# Controller.net
KiCad netlist of a schematic drawn in Altium Designer
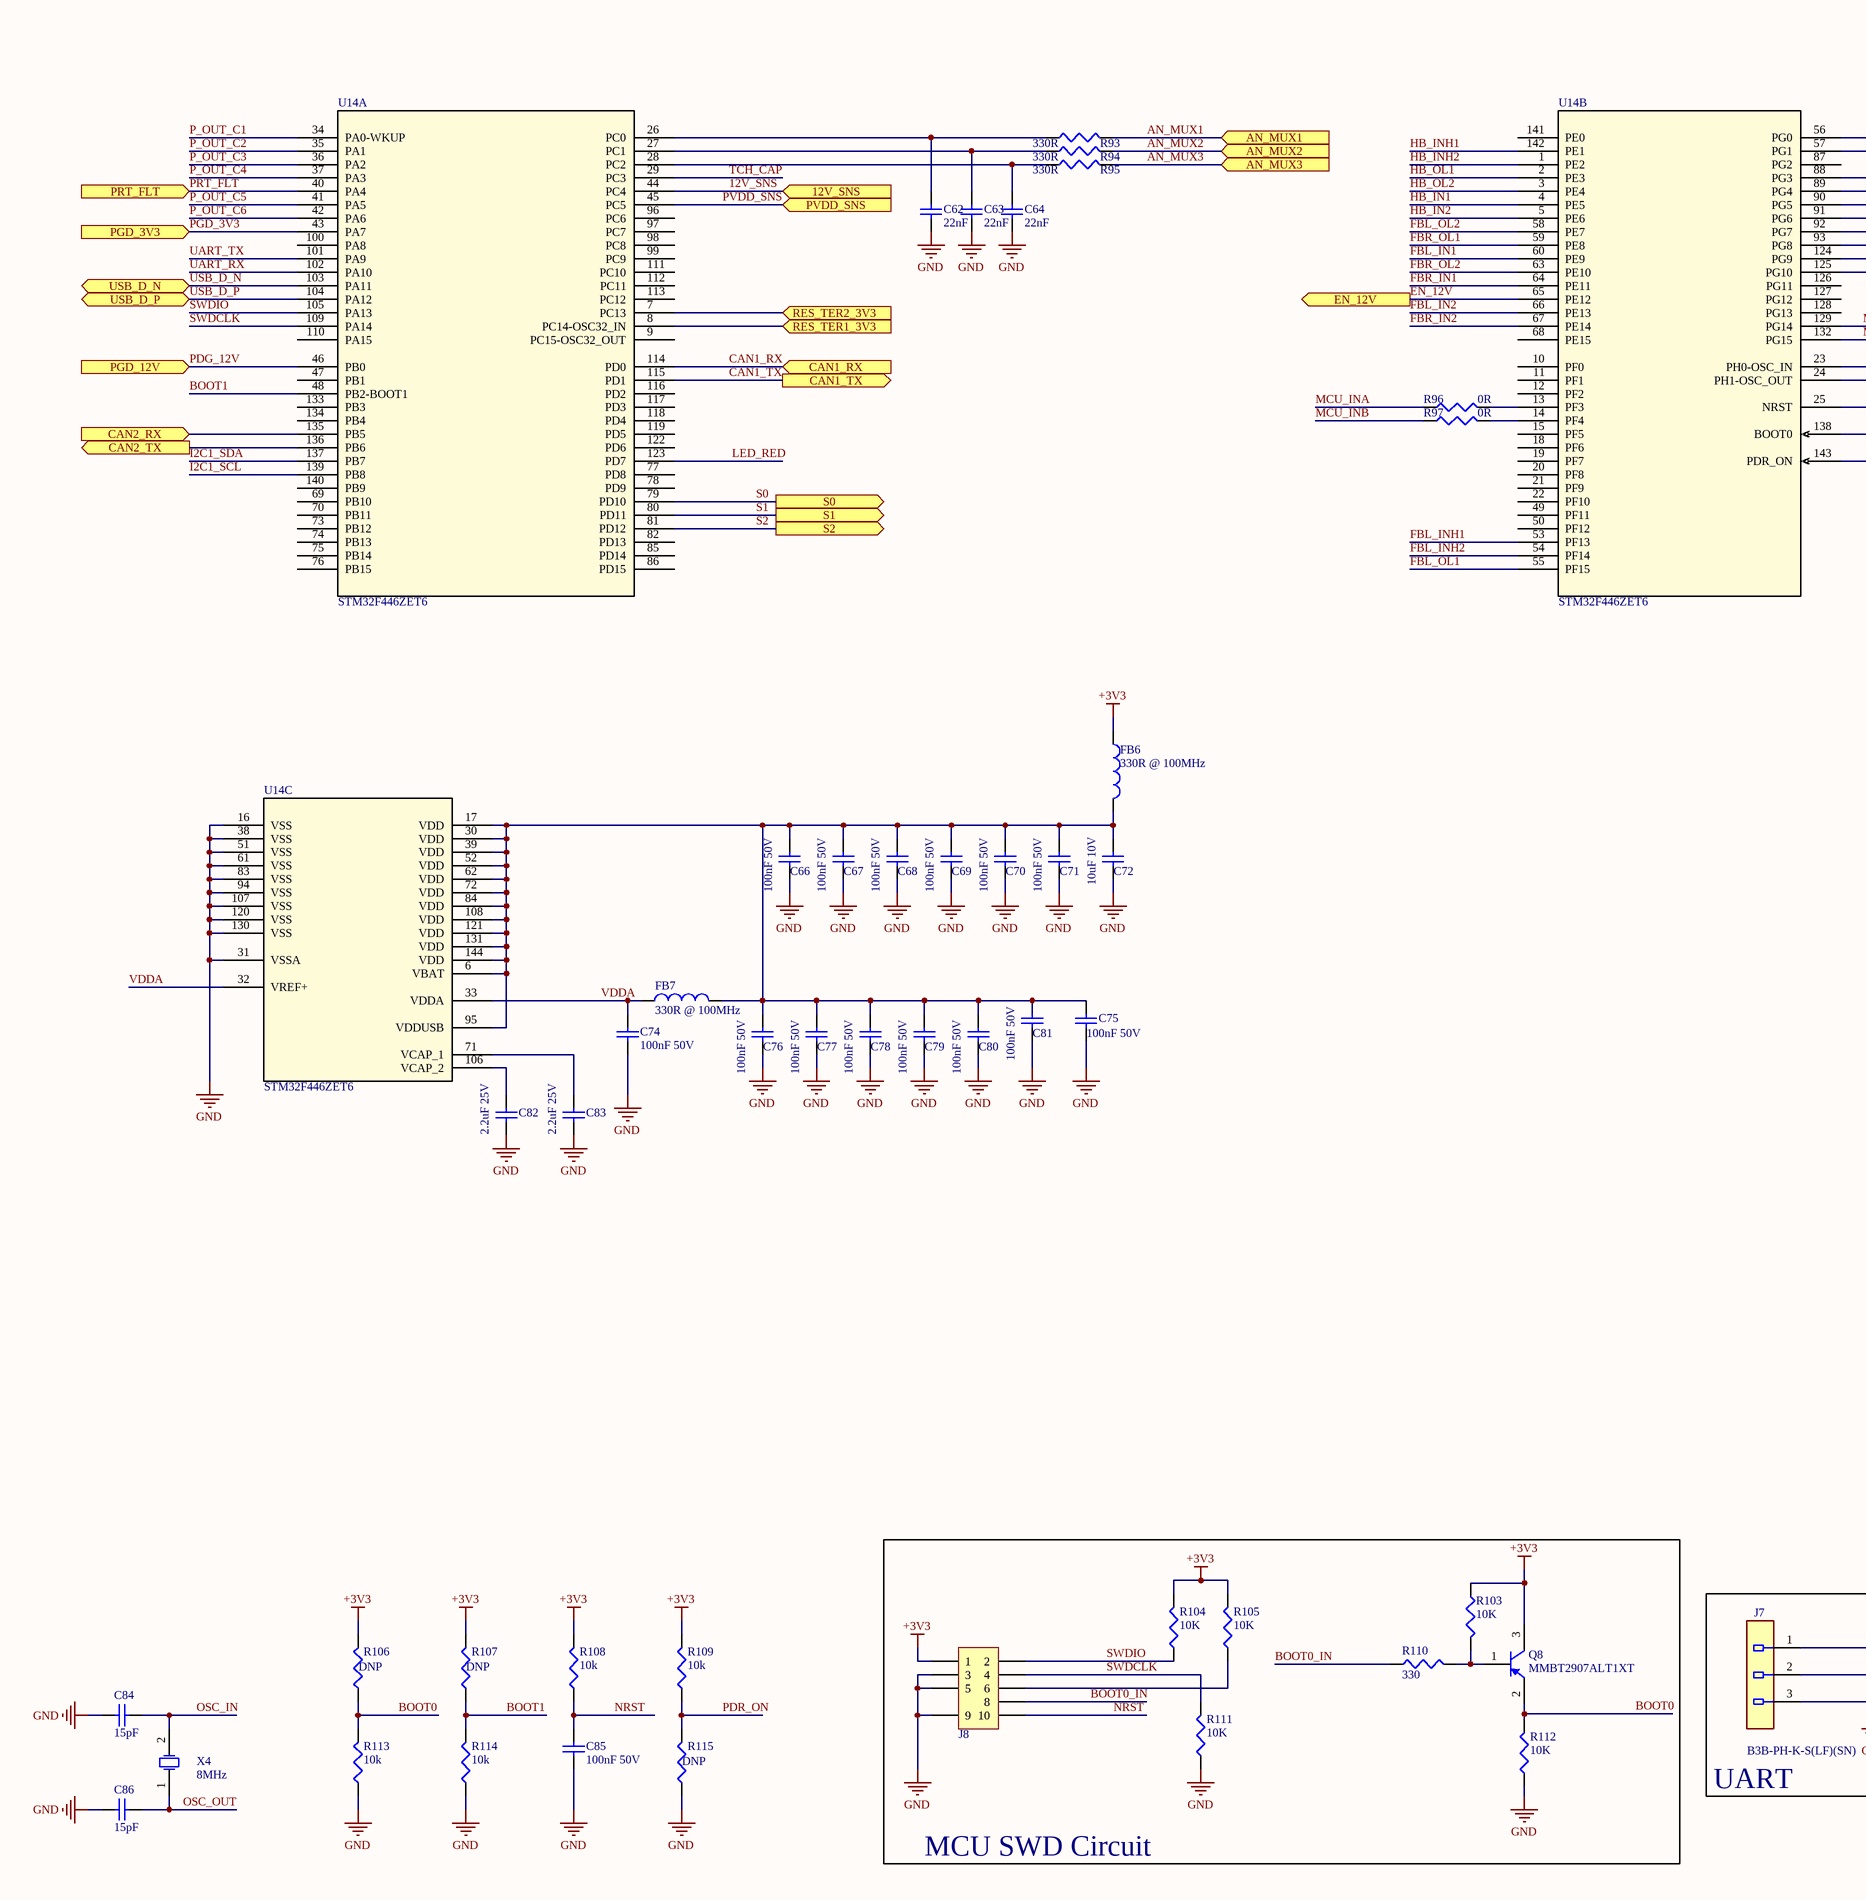
[diagram p0: Controller.SchDoc, left]
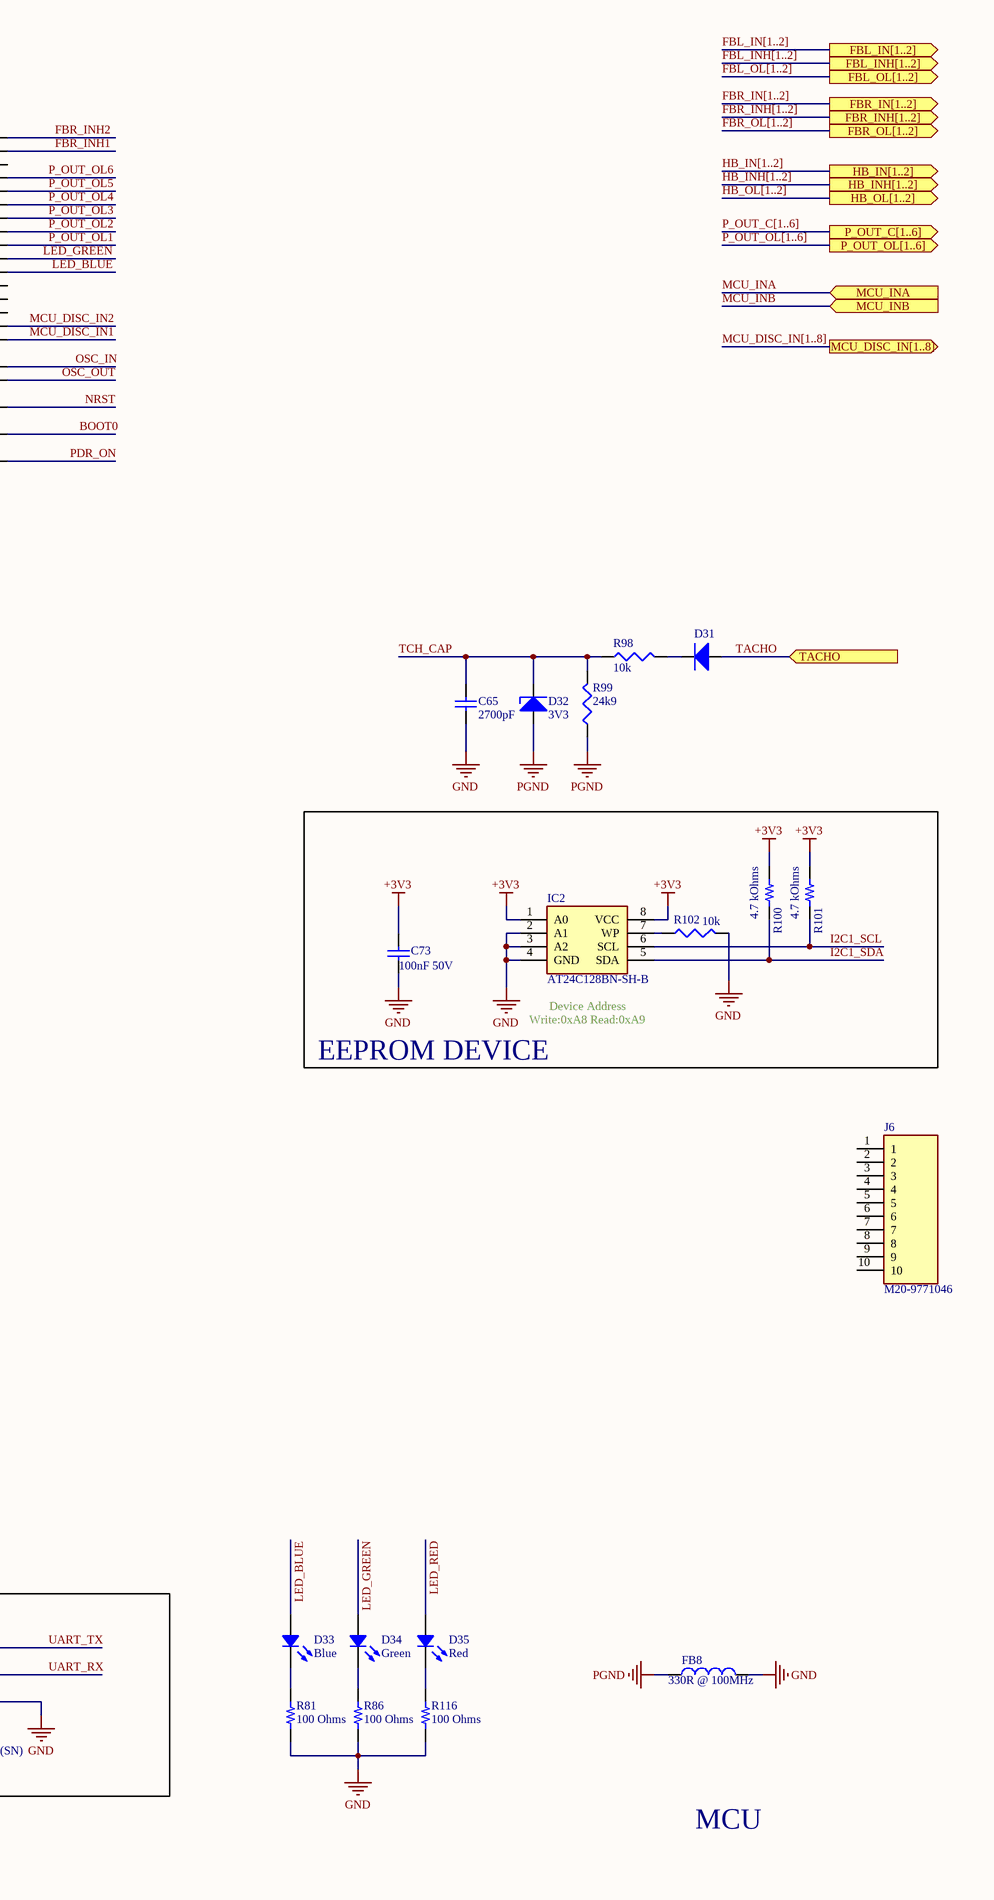
[diagram p1: Controller.SchDoc, right]

(export (version "E")
  (design (tool "Eeschema 10.0.6"))
  (components
    (comp (ref "C62")
      (value "22nF")
      (footprint "CAP0603")
      (description "CAP CER 0.022UF 50V X7R 0603")
      (libsource (lib "CAP_Library") (part "CAP0603_22nF"))
    )
    (comp (ref "C63")
      (value "22nF")
      (footprint "CAP0603")
      (description "CAP CER 0.022UF 50V X7R 0603")
      (libsource (lib "CAP_Library") (part "CAP0603_22nF"))
    )
    (comp (ref "C64")
      (value "22nF")
      (footprint "CAP0603")
      (description "CAP CER 0.022UF 50V X7R 0603")
      (libsource (lib "CAP_Library") (part "CAP0603_22nF"))
    )
    (comp (ref "C65")
      (value "2700pF")
      (footprint "CAP0603")
      (description "CAP CER 1200PF 50V X7R 0603")
      (libsource (lib "CAP_Library") (part "CAP0603_2700pF"))
    )
    (comp (ref "C66")
      (value "100nF 50V")
      (footprint "CAP0603")
      (description "CAP CER 0.1UF 50V X7R 0603")
      (libsource (lib "CAP_Library") (part "CAP0603_100nF"))
    )
    (comp (ref "C67")
      (value "100nF 50V")
      (footprint "CAP0603")
      (description "CAP CER 0.1UF 50V X7R 0603")
      (libsource (lib "CAP_Library") (part "CAP0603_100nF"))
    )
    (comp (ref "C68")
      (value "100nF 50V")
      (footprint "CAP0603")
      (description "CAP CER 0.1UF 50V X7R 0603")
      (libsource (lib "CAP_Library") (part "CAP0603_100nF"))
    )
    (comp (ref "C69")
      (value "100nF 50V")
      (footprint "CAP0603")
      (description "CAP CER 0.1UF 50V X7R 0603")
      (libsource (lib "CAP_Library") (part "CAP0603_100nF"))
    )
    (comp (ref "C70")
      (value "100nF 50V")
      (footprint "CAP0603")
      (description "CAP CER 0.1UF 50V X7R 0603")
      (libsource (lib "CAP_Library") (part "CAP0603_100nF"))
    )
    (comp (ref "C71")
      (value "100nF 50V")
      (footprint "CAP0603")
      (description "CAP CER 0.1UF 50V X7R 0603")
      (libsource (lib "CAP_Library") (part "CAP0603_100nF"))
    )
    (comp (ref "C72")
      (value "10uF 10V")
      (footprint "CAP0805")
      (description "CAP CER 10UF 10V X7R 0805")
      (libsource (lib "CAP_Library") (part "CAP0805_10uF"))
    )
    (comp (ref "C73")
      (value "100nF 50V")
      (footprint "CAP0603")
      (description "CAP CER 0.1UF 50V X7R 0603")
      (libsource (lib "CAP_Library") (part "CAP0603_100nF"))
    )
    (comp (ref "C74")
      (value "100nF 50V")
      (footprint "CAP0603")
      (description "CAP CER 0.1UF 50V X7R 0603")
      (libsource (lib "CAP_Library") (part "CAP0603_100nF"))
    )
    (comp (ref "C75")
      (value "100nF 50V")
      (footprint "CAP0603")
      (description "CAP CER 0.1UF 50V X7R 0603")
      (libsource (lib "CAP_Library") (part "CAP0603_100nF"))
    )
    (comp (ref "C76")
      (value "100nF 50V")
      (footprint "CAP0603")
      (description "CAP CER 0.1UF 50V X7R 0603")
      (libsource (lib "CAP_Library") (part "CAP0603_100nF"))
    )
    (comp (ref "C77")
      (value "100nF 50V")
      (footprint "CAP0603")
      (description "CAP CER 0.1UF 50V X7R 0603")
      (libsource (lib "CAP_Library") (part "CAP0603_100nF"))
    )
    (comp (ref "C78")
      (value "100nF 50V")
      (footprint "CAP0603")
      (description "CAP CER 0.1UF 50V X7R 0603")
      (libsource (lib "CAP_Library") (part "CAP0603_100nF"))
    )
    (comp (ref "C79")
      (value "100nF 50V")
      (footprint "CAP0603")
      (description "CAP CER 0.1UF 50V X7R 0603")
      (libsource (lib "CAP_Library") (part "CAP0603_100nF"))
    )
    (comp (ref "C80")
      (value "100nF 50V")
      (footprint "CAP0603")
      (description "CAP CER 0.1UF 50V X7R 0603")
      (libsource (lib "CAP_Library") (part "CAP0603_100nF"))
    )
    (comp (ref "C81")
      (value "100nF 50V")
      (footprint "CAP0603")
      (description "CAP CER 0.1UF 50V X7R 0603")
      (libsource (lib "CAP_Library") (part "CAP0603_100nF"))
    )
    (comp (ref "C82")
      (value "2.2uF 25V")
      (footprint "CAP0603")
      (description "CAP CER 2.2UF 25V X7S 0603")
      (libsource (lib "CAP_Library") (part "CAP0603_2.2uF"))
    )
    (comp (ref "C83")
      (value "2.2uF 25V")
      (footprint "CAP0603")
      (description "CAP CER 2.2UF 25V X7S 0603")
      (libsource (lib "CAP_Library") (part "CAP0603_2.2uF"))
    )
    (comp (ref "C84")
      (value "15pF")
      (footprint "CAP0603")
      (description "CAP CER 15PF 50V C0G/NP0 0603")
      (libsource (lib "CAP_Library") (part "CAP0603_15pF"))
    )
    (comp (ref "C85")
      (value "100nF 50V")
      (footprint "CAP0603")
      (description "CAP CER 0.1UF 50V X7R 0603")
      (libsource (lib "CAP_Library") (part "CAP0603_100nF"))
    )
    (comp (ref "C86")
      (value "15pF")
      (footprint "CAP0603")
      (description "CAP CER 15PF 50V C0G/NP0 0603")
      (libsource (lib "CAP_Library") (part "CAP0603_15pF"))
    )
    (comp (ref "D31")
      (value "100V 300mA")
      (footprint "SOD123_1N4148W-7-F")
      (description "DIODE GEN PURP 100V 300MA SOD123")
      (libsource (lib "DIODE_Library") (part "DIODE_1N4148W-7-F"))
    )
    (comp (ref "D32")
      (value "3V3")
      (footprint "SOD323")
      (description "DIODE ZENER 3.3V 300MW SOD323")
      (libsource (lib "DIODE_Library") (part "ZENER_3V3_MM3Z3V3T1G"))
    )
    (comp (ref "D33")
      (value "Blue")
      (footprint "LED 0805_2012 BLUE")
      (description "LED BLUE CLEAR 0805 SMD")
      (fields (field (name "PART NUMBER") "IN-S85AT5B") (field (name "MANUFACTURER") "Inolux"))
      (libsource (lib "Celestial Altium Library") (part "LED"))
    )
    (comp (ref "D34")
      (value "Green")
      (footprint "LED 0805_2012 GREEN")
      (description "LED GREEN CLEAR 0805 SMD")
      (fields
        (field (name "PART NUMBER") "QTLP630C4TR")
        (field (name "MANUFACTURER") "Everlight Electronics Co Ltd")
      )
      (libsource (lib "Celestial Altium Library") (part "LED"))
    )
    (comp (ref "D35")
      (value "Red")
      (footprint "LED 0805_2012 RED")
      (description "LED RED CLEAR CHIP SMD")
      (fields (field (name "PART NUMBER") "APT2012EC") (field (name "MANUFACTURER") "Kingbright"))
      (libsource (lib "Celestial Altium Library") (part "LED"))
    )
    (comp (ref "FB6")
      (value "330R @ 100MHz")
      (footprint "FB0603")
      (description "FERRITE BEAD 330 OHM 0603 1LN")
      (libsource (lib "") (part "FB0603_330R@100MHz_1"))
    )
    (comp (ref "FB7")
      (value "330R @ 100MHz")
      (footprint "FB0603")
      (description "FERRITE BEAD 330 OHM 0603 1LN")
      (libsource (lib "") (part "FB0603_330R@100MHz_1"))
    )
    (comp (ref "FB8")
      (value "330R @ 100MHz")
      (footprint "FB0603")
      (description "FERRITE BEAD 330 OHM 0603 1LN")
      (libsource (lib "FB_Library") (part "FB0603_330R@100MHz"))
    )
    (comp (ref "IC2")
      (value "AT24C128BN-SH-B")
      (footprint "SamacSys:SOIC127P600X175-8N")
      (description "Integrated Circuit")
      (fields (field (name "MOUSER PART NUMBER") "556-A24C128BNSH-B"))
      (libsource (lib "SamacSys") (part "AT24C128BN-SH-B"))
    )
    (comp (ref "J6")
      (value "M20-9771046")
      (footprint "SamacSys:HDRV10W66P0X254_1X10_2540X254X844P")
      (description "Connector")
      (fields (field (name "MOUSER PART NUMBER") "855-M20-9771046"))
      (libsource (lib "*") (part "M20-9771046"))
    )
    (comp (ref "J7")
      (value "B3B-PH-K-S_LF_SN")
      (footprint "JST_B3B-PH-K-S_LF_SN_0")
      (fields (field (name "MANUFACTURER PART NUMBER") "B3B-PH-K-S(LF)(SN)"))
      (libsource (lib "MYiR-T507") (part "B3B-PH-K-S_LF_SN"))
    )
    (comp (ref "J8")
      (value "9 pos")
      (footprint "FTSH-105-01-F-DV-007-K-P")
      (description "CONN HEADER 9 POS DUAL .05\" SMD")
      (libsource (lib "CON_Library") (part "FTSH-105-01-F-DV-007-K-P"))
    )
    (comp (ref "Q8")
      (value "MMBT2907ALT1XT")
      (footprint "SOT95P245X110-3N")
      (description "Bipolar Transistors - BJT AF TRANS GP BJT PNP 60V 0.6A")
      (libsource (lib "SMALL_BCM_LIB") (part "MMBT2907ALT1XT"))
    )
    (comp (ref "R81")
      (value "100 Ohms")
      (footprint "RES 0805_2012")
      (description "RES 100 OHM 5% 1/4W 0805")
      (fields
        (field (name "PART NUMBER") "RK73B2ATTD101J")
        (field (name "MANUFACTURER") "KOA Speer Electronics, Inc.")
      )
      (libsource (lib "Celestial Altium Library") (part "Resistor"))
    )
    (comp (ref "R86")
      (value "100 Ohms")
      (footprint "RES 0805_2012")
      (description "RES 100 OHM 5% 1/4W 0805")
      (fields
        (field (name "PART NUMBER") "RK73B2ATTD101J")
        (field (name "MANUFACTURER") "KOA Speer Electronics, Inc.")
      )
      (libsource (lib "Celestial Altium Library") (part "Resistor"))
    )
    (comp (ref "R93")
      (value "330R")
      (footprint "RES0603")
      (description "RES 330 OHM 1% 1/10W 0603")
      (libsource (lib "RES_Library") (part "RES0603_330R"))
    )
    (comp (ref "R94")
      (value "330R")
      (footprint "RES0603")
      (description "RES 330 OHM 1% 1/10W 0603")
      (libsource (lib "RES_Library") (part "RES0603_330R"))
    )
    (comp (ref "R95")
      (value "330R")
      (footprint "RES0603")
      (description "RES 330 OHM 1% 1/10W 0603")
      (libsource (lib "RES_Library") (part "RES0603_330R"))
    )
    (comp (ref "R96")
      (value "0R")
      (footprint "RES0603")
      (description "RES SMD 0 OHM JUMPER 1/10W 0603")
      (libsource (lib "RES_Library") (part "RES0603_0R"))
    )
    (comp (ref "R97")
      (value "0R")
      (footprint "RES0603")
      (description "RES SMD 0 OHM JUMPER 1/10W 0603")
      (libsource (lib "RES_Library") (part "RES0603_0R"))
    )
    (comp (ref "R98")
      (value "10k")
      (footprint "RES0603")
      (description "RES SMD 10K OHM 5% 1/10W 0603")
      (libsource (lib "RES_Library") (part "RES0603_10k"))
    )
    (comp (ref "R99")
      (value "24k9")
      (footprint "RES0603")
      (description "RES SMD 24.9K OHM 1% 1/10W 0603")
      (libsource (lib "RES_Library") (part "RES0603_24k9"))
    )
    (comp (ref "R100")
      (value "4.7 kOhms")
      (footprint "RES 0603_1608")
      (description "RES 4.7K OHM 5% 1/10W 0603")
      (fields
        (field (name "PART NUMBER") "RK73B1JTTD472J")
        (field (name "MANUFACTURER") "KOA Speer Electronics, Inc.")
      )
      (libsource (lib "Celestial Altium Library") (part "Resistor"))
    )
    (comp (ref "R101")
      (value "4.7 kOhms")
      (footprint "RES 0603_1608")
      (description "RES 4.7K OHM 5% 1/10W 0603")
      (fields
        (field (name "PART NUMBER") "RK73B1JTTD472J")
        (field (name "MANUFACTURER") "KOA Speer Electronics, Inc.")
      )
      (libsource (lib "Celestial Altium Library") (part "Resistor"))
    )
    (comp (ref "R102")
      (value "10k")
      (footprint "RES0603")
      (description "RES SMD 10K OHM 5% 1/10W 0603")
      (libsource (lib "RES_Library") (part "RES0603_10k"))
    )
    (comp (ref "R103")
      (value "10K")
      (footprint "R 0603(1608)")
      (description "Res General Purpose Thick Film 0603 10K Ohm 1% 1/10W ±100ppm/°C Molded SMD Paper T/R")
      (fields
        (field (name "MANUFACTURER") "Yageo")
        (field (name "MANUFACTURER PART NUMBER") "RC0603FR-0710KL")
      )
      (libsource (lib "Miscellaneous Devices") (part "Res3"))
    )
    (comp (ref "R104")
      (value "10K")
      (footprint "R 0603(1608)")
      (description "Res General Purpose Thick Film 0603 10K Ohm 1% 1/10W ±100ppm/°C Molded SMD Paper T/R")
      (fields
        (field (name "MANUFACTURER") "Yageo")
        (field (name "MANUFACTURER PART NUMBER") "RC0603FR-0710KL")
      )
      (libsource (lib "Miscellaneous Devices") (part "Res3"))
    )
    (comp (ref "R105")
      (value "10K")
      (footprint "R 0603(1608)")
      (description "Res General Purpose Thick Film 0603 10K Ohm 1% 1/10W ±100ppm/°C Molded SMD Paper T/R")
      (fields
        (field (name "MANUFACTURER") "Yageo")
        (field (name "MANUFACTURER PART NUMBER") "RC0603FR-0710KL")
      )
      (libsource (lib "Miscellaneous Devices") (part "Res3"))
    )
    (comp (ref "R106")
      (value "10k")
      (footprint "RES0603")
      (description "RES SMD 10K OHM 5% 1/10W 0603")
      (fields (field (name "ASSEMBLY") "DNP"))
      (libsource (lib "RES_Library") (part "RES0603_10k"))
    )
    (comp (ref "R107")
      (value "10k")
      (footprint "RES0603")
      (description "RES SMD 10K OHM 5% 1/10W 0603")
      (fields (field (name "ASSEMBLY") "DNP"))
      (libsource (lib "RES_Library") (part "RES0603_10k"))
    )
    (comp (ref "R108")
      (value "10k")
      (footprint "RES0603")
      (description "RES SMD 10K OHM 5% 1/10W 0603")
      (libsource (lib "RES_Library") (part "RES0603_10k"))
    )
    (comp (ref "R109")
      (value "10k")
      (footprint "RES0603")
      (description "RES SMD 10K OHM 5% 1/10W 0603")
      (libsource (lib "RES_Library") (part "RES0603_10k"))
    )
    (comp (ref "R110")
      (value "330")
      (footprint "R 0603(1608)")
      (description "YAGEO (PHYCOMP) - RC0603FR-07330RL - RES, THICK FILM, 330R, 1%, 0.1W, 0603")
      (fields
        (field (name "MANUFACTURER") "Yageo")
        (field (name "MANUFACTURER PART NUMBER") "RC0603FR-07330RL")
      )
      (libsource (lib "Miscellaneous Devices") (part "Res3"))
    )
    (comp (ref "R111")
      (value "10K")
      (footprint "R 0603(1608)")
      (description "Res General Purpose Thick Film 0603 10K Ohm 1% 1/10W ±100ppm/°C Molded SMD Paper T/R")
      (fields
        (field (name "MANUFACTURER") "Yageo")
        (field (name "MANUFACTURER PART NUMBER") "RC0603FR-0710KL")
      )
      (libsource (lib "Miscellaneous Devices") (part "Res3"))
    )
    (comp (ref "R112")
      (value "10K")
      (footprint "R 0603(1608)")
      (description "Res General Purpose Thick Film 0603 10K Ohm 1% 1/10W ±100ppm/°C Molded SMD Paper T/R")
      (fields
        (field (name "MANUFACTURER") "Yageo")
        (field (name "MANUFACTURER PART NUMBER") "RC0603FR-0710KL")
      )
      (libsource (lib "Miscellaneous Devices") (part "Res3"))
    )
    (comp (ref "R113")
      (value "10k")
      (footprint "RES0603")
      (description "RES SMD 10K OHM 5% 1/10W 0603")
      (libsource (lib "RES_Library") (part "RES0603_10k"))
    )
    (comp (ref "R114")
      (value "10k")
      (footprint "RES0603")
      (description "RES SMD 10K OHM 5% 1/10W 0603")
      (libsource (lib "RES_Library") (part "RES0603_10k"))
    )
    (comp (ref "R115")
      (value "10k")
      (footprint "RES0603")
      (description "RES SMD 10K OHM 5% 1/10W 0603")
      (fields (field (name "ASSEMBLY") "DNP"))
      (libsource (lib "RES_Library") (part "RES0603_10k"))
    )
    (comp (ref "R116")
      (value "100 Ohms")
      (footprint "RES 0805_2012")
      (description "RES 100 OHM 5% 1/4W 0805")
      (fields
        (field (name "PART NUMBER") "RK73B2ATTD101J")
        (field (name "MANUFACTURER") "KOA Speer Electronics, Inc.")
      )
      (libsource (lib "Celestial Altium Library") (part "Resistor"))
    )
    (comp (ref "U14")
      (value "STM32F446ZET6")
      (footprint "LQFP144-20x20mm")
      (description "No Description Available")
      (fields (field (name "COPYRIGHT") "Copyright (C) 2022 Ultra Librarian. All rights reserved."))
      (libsource (lib "STM32F446ZET6") (part "STM32F446ZET6"))
    )
    (comp (ref "X4")
      (value "8MHz")
      (footprint "CRY_NX8045GB")
      (description "CRYSTAL 8.0000MHZ 8PF SMD")
      (libsource (lib "MISC_Library") (part "CRY_NX8045GB-8.000M-STD-CSJ-1"))
    )
  )
  (nets
    (net (code "7") (name "+3V3") (class "Default")
      (node (ref "C73") (pin "2") (pinfunction "2_2") (pintype "passive"))
      (node (ref "FB6") (pin "2") (pinfunction "2_2") (pintype "passive"))
      (node (ref "IC2") (pin "1") (pinfunction "A0_1") (pintype "passive"))
      (node (ref "IC2") (pin "8") (pinfunction "VCC_8") (pintype "passive"))
      (node (ref "J8") (pin "1") (pinfunction "1_1") (pintype "passive"))
      (node (ref "Q8") (pin "3") (pinfunction "C_3") (pintype "passive"))
      (node (ref "R100") (pin "2") (pinfunction "2_2") (pintype "passive"))
      (node (ref "R101") (pin "2") (pinfunction "2_2") (pintype "passive"))
      (node (ref "R103") (pin "2") (pinfunction "2_2") (pintype "passive"))
      (node (ref "R104") (pin "1") (pinfunction "1_1") (pintype "passive"))
      (node (ref "R105") (pin "1") (pinfunction "1_1") (pintype "passive"))
      (node (ref "R106") (pin "2") (pinfunction "2_2") (pintype "passive"))
      (node (ref "R107") (pin "2") (pinfunction "2_2") (pintype "passive"))
      (node (ref "R108") (pin "2") (pinfunction "2_2") (pintype "passive"))
      (node (ref "R109") (pin "2") (pinfunction "2_2") (pintype "passive"))
    )
    (net (code "8") (name "/12V_SNS") (class "Default")
      (node (ref "U14") (pin "44") (pinfunction "PC4_44") (pintype "passive"))
    )
    (net (code "9") (name "/AN_MUX1") (class "Default")
      (node (ref "R93") (pin "2") (pinfunction "2_2") (pintype "passive"))
    )
    (net (code "10") (name "/AN_MUX2") (class "Default")
      (node (ref "R94") (pin "2") (pinfunction "2_2") (pintype "passive"))
    )
    (net (code "11") (name "/AN_MUX3") (class "Default")
      (node (ref "R95") (pin "2") (pinfunction "2_2") (pintype "passive"))
    )
    (net (code "12") (name "/BOOT0") (class "Default")
      (node (ref "Q8") (pin "2") (pinfunction "E_2") (pintype "passive"))
      (node (ref "R106") (pin "1") (pinfunction "1_1") (pintype "passive"))
      (node (ref "R112") (pin "2") (pinfunction "2_2") (pintype "passive"))
      (node (ref "R113") (pin "2") (pinfunction "2_2") (pintype "passive"))
      (node (ref "U14") (pin "138") (pinfunction "BOOT0_138") (pintype "input"))
    )
    (net (code "13") (name "/BOOT0_IN") (class "Default")
      (node (ref "J8") (pin "8") (pinfunction "8_8") (pintype "passive"))
      (node (ref "R110") (pin "2") (pinfunction "2_2") (pintype "passive"))
    )
    (net (code "14") (name "/BOOT1") (class "Default")
      (node (ref "R107") (pin "1") (pinfunction "1_1") (pintype "passive"))
      (node (ref "R114") (pin "2") (pinfunction "2_2") (pintype "passive"))
      (node (ref "U14") (pin "48") (pinfunction "PB2-BOOT1_48") (pintype "passive"))
    )
    (net (code "15") (name "/CAN1_RX") (class "Default")
      (node (ref "U14") (pin "114") (pinfunction "PD0_114") (pintype "passive"))
    )
    (net (code "16") (name "/CAN1_TX") (class "Default")
      (node (ref "U14") (pin "115") (pinfunction "PD1_115") (pintype "passive"))
    )
    (net (code "17") (name "/CAN2_RX") (class "Default")
      (node (ref "U14") (pin "135") (pinfunction "PB5_135") (pintype "passive"))
    )
    (net (code "18") (name "/CAN2_TX") (class "Default")
      (node (ref "U14") (pin "136") (pinfunction "PB6_136") (pintype "passive"))
    )
    (net (code "19") (name "/EN_12V") (class "Default")
      (node (ref "U14") (pin "65") (pinfunction "PE12_65") (pintype "passive"))
    )
    (net (code "20") (name "/FBL_IN1") (class "Default")
      (node (ref "U14") (pin "60") (pinfunction "PE9_60") (pintype "passive"))
    )
    (net (code "21") (name "/FBL_IN2") (class "Default")
      (node (ref "U14") (pin "66") (pinfunction "PE13_66") (pintype "passive"))
    )
    (net (code "22") (name "/FBL_INH1") (class "Default")
      (node (ref "U14") (pin "53") (pinfunction "PF13_53") (pintype "passive"))
    )
    (net (code "23") (name "/FBL_INH2") (class "Default")
      (node (ref "U14") (pin "54") (pinfunction "PF14_54") (pintype "passive"))
    )
    (net (code "26") (name "/FBL_OL1") (class "Default")
      (node (ref "U14") (pin "55") (pinfunction "PF15_55") (pintype "passive"))
    )
    (net (code "27") (name "/FBL_OL2") (class "Default")
      (node (ref "U14") (pin "58") (pinfunction "PE7_58") (pintype "passive"))
    )
    (net (code "29") (name "/FBR_IN1") (class "Default")
      (node (ref "U14") (pin "64") (pinfunction "PE11_64") (pintype "passive"))
    )
    (net (code "30") (name "/FBR_IN2") (class "Default")
      (node (ref "U14") (pin "67") (pinfunction "PE14_67") (pintype "passive"))
    )
    (net (code "31") (name "/FBR_INH1") (class "Default")
      (node (ref "U14") (pin "57") (pinfunction "PG1_57") (pintype "passive"))
    )
    (net (code "32") (name "/FBR_INH2") (class "Default")
      (node (ref "U14") (pin "56") (pinfunction "PG0_56") (pintype "passive"))
    )
    (net (code "35") (name "/FBR_OL1") (class "Default")
      (node (ref "U14") (pin "59") (pinfunction "PE8_59") (pintype "passive"))
    )
    (net (code "36") (name "/FBR_OL2") (class "Default")
      (node (ref "U14") (pin "63") (pinfunction "PE10_63") (pintype "passive"))
    )
    (net (code "38") (name "/HB_IN1") (class "Default")
      (node (ref "U14") (pin "4") (pinfunction "PE5_4") (pintype "passive"))
    )
    (net (code "39") (name "/HB_IN2") (class "Default")
      (node (ref "U14") (pin "5") (pinfunction "PE6_5") (pintype "passive"))
    )
    (net (code "40") (name "/HB_INH1") (class "Default")
      (node (ref "U14") (pin "142") (pinfunction "PE1_142") (pintype "passive"))
    )
    (net (code "41") (name "/HB_INH2") (class "Default")
      (node (ref "U14") (pin "1") (pinfunction "PE2_1") (pintype "passive"))
    )
    (net (code "44") (name "/HB_OL1") (class "Default")
      (node (ref "U14") (pin "2") (pinfunction "PE3_2") (pintype "passive"))
    )
    (net (code "45") (name "/HB_OL2") (class "Default")
      (node (ref "U14") (pin "3") (pinfunction "PE4_3") (pintype "passive"))
    )
    (net (code "47") (name "/I2C1_SCL") (class "Default")
      (node (ref "IC2") (pin "6") (pinfunction "SCL_6") (pintype "passive"))
      (node (ref "R101") (pin "1") (pinfunction "1_1") (pintype "passive"))
      (node (ref "U14") (pin "139") (pinfunction "PB8_139") (pintype "passive"))
    )
    (net (code "48") (name "/I2C1_SDA") (class "Default")
      (node (ref "IC2") (pin "5") (pinfunction "SDA_5") (pintype "passive"))
      (node (ref "R100") (pin "1") (pinfunction "1_1") (pintype "passive"))
      (node (ref "U14") (pin "137") (pinfunction "PB7_137") (pintype "passive"))
    )
    (net (code "49") (name "/LED_BLUE") (class "Default")
      (node (ref "D33") (pin "1") (pinfunction "1_1") (pintype "passive"))
      (node (ref "U14") (pin "125") (pinfunction "PG10_125") (pintype "passive"))
    )
    (net (code "50") (name "/LED_GREEN") (class "Default")
      (node (ref "D34") (pin "1") (pinfunction "1_1") (pintype "passive"))
      (node (ref "U14") (pin "124") (pinfunction "PG9_124") (pintype "passive"))
    )
    (net (code "51") (name "/LED_RED") (class "Default")
      (node (ref "D35") (pin "1") (pinfunction "1_1") (pintype "passive"))
      (node (ref "U14") (pin "123") (pinfunction "PD7_123") (pintype "passive"))
    )
    (net (code "52") (name "/MCU_DISC_IN1") (class "Default")
      (node (ref "U14") (pin "132") (pinfunction "PG15_132") (pintype "passive"))
    )
    (net (code "53") (name "/MCU_DISC_IN2") (class "Default")
      (node (ref "U14") (pin "129") (pinfunction "PG14_129") (pintype "passive"))
    )
    (net (code "55") (name "/MCU_INA") (class "Default")
      (node (ref "R96") (pin "1") (pinfunction "1_1") (pintype "passive"))
    )
    (net (code "56") (name "/MCU_INB") (class "Default")
      (node (ref "R97") (pin "1") (pinfunction "1_1") (pintype "passive"))
    )
    (net (code "57") (name "/NRST") (class "Default")
      (node (ref "C85") (pin "2") (pinfunction "2_2") (pintype "passive"))
      (node (ref "J8") (pin "10") (pinfunction "10_10") (pintype "passive"))
      (node (ref "R108") (pin "1") (pinfunction "1_1") (pintype "passive"))
      (node (ref "U14") (pin "25") (pinfunction "NRST_25") (pintype "passive"))
    )
    (net (code "58") (name "/OSC_IN") (class "Default")
      (node (ref "C84") (pin "2") (pinfunction "2_2") (pintype "passive"))
      (node (ref "U14") (pin "23") (pinfunction "PH0-OSC_IN_23") (pintype "passive"))
      (node (ref "X4") (pin "2") (pinfunction "OSC2_2") (pintype "passive"))
    )
    (net (code "59") (name "/OSC_OUT") (class "Default")
      (node (ref "C86") (pin "2") (pinfunction "2_2") (pintype "passive"))
      (node (ref "U14") (pin "24") (pinfunction "PH1-OSC_OUT_24") (pintype "passive"))
      (node (ref "X4") (pin "1") (pinfunction "OSC1_1") (pintype "passive"))
    )
    (net (code "60") (name "/PDG_12V") (class "Default")
      (node (ref "U14") (pin "46") (pinfunction "PB0_46") (pintype "passive"))
    )
    (net (code "61") (name "/PDR_ON") (class "Default")
      (node (ref "R109") (pin "1") (pinfunction "1_1") (pintype "passive"))
      (node (ref "R115") (pin "2") (pinfunction "2_2") (pintype "passive"))
      (node (ref "U14") (pin "143") (pinfunction "PDR_ON_143") (pintype "input"))
    )
    (net (code "62") (name "/PGD_3V3") (class "Default")
      (node (ref "U14") (pin "43") (pinfunction "PA7_43") (pintype "passive"))
    )
    (net (code "63") (name "/PRT_FLT") (class "Default")
      (node (ref "U14") (pin "40") (pinfunction "PA4_40") (pintype "passive"))
    )
    (net (code "64") (name "/PVDD_SNS") (class "Default")
      (node (ref "U14") (pin "45") (pinfunction "PC5_45") (pintype "passive"))
    )
    (net (code "65") (name "/P_OUT_C1") (class "Default")
      (node (ref "U14") (pin "34") (pinfunction "PA0-WKUP_34") (pintype "passive"))
    )
    (net (code "66") (name "/P_OUT_C2") (class "Default")
      (node (ref "U14") (pin "35") (pinfunction "PA1_35") (pintype "passive"))
    )
    (net (code "67") (name "/P_OUT_C3") (class "Default")
      (node (ref "U14") (pin "36") (pinfunction "PA2_36") (pintype "passive"))
    )
    (net (code "68") (name "/P_OUT_C4") (class "Default")
      (node (ref "U14") (pin "37") (pinfunction "PA3_37") (pintype "passive"))
    )
    (net (code "69") (name "/P_OUT_C5") (class "Default")
      (node (ref "U14") (pin "41") (pinfunction "PA5_41") (pintype "passive"))
    )
    (net (code "70") (name "/P_OUT_C6") (class "Default")
      (node (ref "U14") (pin "42") (pinfunction "PA6_42") (pintype "passive"))
    )
    (net (code "72") (name "/P_OUT_OL1") (class "Default")
      (node (ref "U14") (pin "93") (pinfunction "PG8_93") (pintype "passive"))
    )
    (net (code "73") (name "/P_OUT_OL2") (class "Default")
      (node (ref "U14") (pin "92") (pinfunction "PG7_92") (pintype "passive"))
    )
    (net (code "74") (name "/P_OUT_OL3") (class "Default")
      (node (ref "U14") (pin "91") (pinfunction "PG6_91") (pintype "passive"))
    )
    (net (code "75") (name "/P_OUT_OL4") (class "Default")
      (node (ref "U14") (pin "90") (pinfunction "PG5_90") (pintype "passive"))
    )
    (net (code "76") (name "/P_OUT_OL5") (class "Default")
      (node (ref "U14") (pin "89") (pinfunction "PG4_89") (pintype "passive"))
    )
    (net (code "77") (name "/P_OUT_OL6") (class "Default")
      (node (ref "U14") (pin "88") (pinfunction "PG3_88") (pintype "passive"))
    )
    (net (code "79") (name "/RES_TER1_3V3") (class "Default")
      (node (ref "U14") (pin "8") (pinfunction "PC14-OSC32_IN_8") (pintype "passive"))
    )
    (net (code "80") (name "/RES_TER2_3V3") (class "Default")
      (node (ref "U14") (pin "7") (pinfunction "PC13_7") (pintype "passive"))
    )
    (net (code "81") (name "/S0") (class "Default")
      (node (ref "U14") (pin "79") (pinfunction "PD10_79") (pintype "passive"))
    )
    (net (code "82") (name "/S1") (class "Default")
      (node (ref "U14") (pin "80") (pinfunction "PD11_80") (pintype "passive"))
    )
    (net (code "83") (name "/S2") (class "Default")
      (node (ref "U14") (pin "81") (pinfunction "PD12_81") (pintype "passive"))
    )
    (net (code "84") (name "/SWDCLK") (class "Default")
      (node (ref "J8") (pin "4") (pinfunction "4_4") (pintype "passive"))
      (node (ref "R111") (pin "1") (pinfunction "1_1") (pintype "passive"))
      (node (ref "U14") (pin "109") (pinfunction "PA14_109") (pintype "passive"))
    )
    (net (code "85") (name "/SWDIO") (class "Default")
      (node (ref "J8") (pin "2") (pinfunction "2_2") (pintype "passive"))
      (node (ref "R104") (pin "2") (pinfunction "2_2") (pintype "passive"))
      (node (ref "U14") (pin "105") (pinfunction "PA13_105") (pintype "passive"))
    )
    (net (code "86") (name "/TACHO") (class "Default")
      (node (ref "D31") (pin "1") (pinfunction "A_1") (pintype "passive"))
    )
    (net (code "87") (name "/TCH_CAP") (class "Default")
      (node (ref "C65") (pin "2") (pinfunction "2_2") (pintype "passive"))
      (node (ref "D32") (pin "1") (pinfunction "K_1") (pintype "passive"))
      (node (ref "R98") (pin "1") (pinfunction "1_1") (pintype "passive"))
      (node (ref "R99") (pin "2") (pinfunction "2_2") (pintype "passive"))
      (node (ref "U14") (pin "29") (pinfunction "PC3_29") (pintype "passive"))
    )
    (net (code "88") (name "/UART_RX") (class "Default")
      (node (ref "J7") (pin "2") (pinfunction "2_2") (pintype "passive"))
      (node (ref "U14") (pin "102") (pinfunction "PA10_102") (pintype "passive"))
    )
    (net (code "89") (name "/UART_TX") (class "Default")
      (node (ref "J7") (pin "1") (pinfunction "1_1") (pintype "passive"))
      (node (ref "U14") (pin "101") (pinfunction "PA9_101") (pintype "passive"))
    )
    (net (code "90") (name "/USB_D_N") (class "Default")
      (node (ref "U14") (pin "103") (pinfunction "PA11_103") (pintype "passive"))
    )
    (net (code "91") (name "/USB_D_P") (class "Default")
      (node (ref "U14") (pin "104") (pinfunction "PA12_104") (pintype "passive"))
    )
    (net (code "92") (name "/VDDA") (class "Default")
      (node (ref "C74") (pin "2") (pinfunction "2_2") (pintype "passive"))
      (node (ref "FB7") (pin "2") (pinfunction "2_2") (pintype "passive"))
      (node (ref "U14") (pin "32") (pinfunction "VREF+_32") (pintype "power_in"))
      (node (ref "U14") (pin "33") (pinfunction "VDDA_33") (pintype "power_in"))
    )
    (net (code "93") (name "GND") (class "Default")
      (node (ref "C62") (pin "2") (pinfunction "2_2") (pintype "passive"))
      (node (ref "C63") (pin "2") (pinfunction "2_2") (pintype "passive"))
      (node (ref "C64") (pin "2") (pinfunction "2_2") (pintype "passive"))
      (node (ref "C65") (pin "1") (pinfunction "1_1") (pintype "passive"))
      (node (ref "C66") (pin "1") (pinfunction "1_1") (pintype "passive"))
      (node (ref "C67") (pin "1") (pinfunction "1_1") (pintype "passive"))
      (node (ref "C68") (pin "1") (pinfunction "1_1") (pintype "passive"))
      (node (ref "C69") (pin "1") (pinfunction "1_1") (pintype "passive"))
      (node (ref "C70") (pin "1") (pinfunction "1_1") (pintype "passive"))
      (node (ref "C71") (pin "1") (pinfunction "1_1") (pintype "passive"))
      (node (ref "C72") (pin "1") (pinfunction "1_1") (pintype "passive"))
      (node (ref "C73") (pin "1") (pinfunction "1_1") (pintype "passive"))
      (node (ref "C74") (pin "1") (pinfunction "1_1") (pintype "passive"))
      (node (ref "C75") (pin "1") (pinfunction "1_1") (pintype "passive"))
      (node (ref "C76") (pin "1") (pinfunction "1_1") (pintype "passive"))
      (node (ref "C77") (pin "1") (pinfunction "1_1") (pintype "passive"))
      (node (ref "C78") (pin "1") (pinfunction "1_1") (pintype "passive"))
      (node (ref "C79") (pin "1") (pinfunction "1_1") (pintype "passive"))
      (node (ref "C80") (pin "1") (pinfunction "1_1") (pintype "passive"))
      (node (ref "C81") (pin "1") (pinfunction "1_1") (pintype "passive"))
      (node (ref "C82") (pin "1") (pinfunction "1_1") (pintype "passive"))
      (node (ref "C83") (pin "1") (pinfunction "1_1") (pintype "passive"))
      (node (ref "C84") (pin "1") (pinfunction "1_1") (pintype "passive"))
      (node (ref "C85") (pin "1") (pinfunction "1_1") (pintype "passive"))
      (node (ref "C86") (pin "1") (pinfunction "1_1") (pintype "passive"))
      (node (ref "FB8") (pin "2") (pinfunction "2_2") (pintype "passive"))
      (node (ref "IC2") (pin "2") (pinfunction "A1_2") (pintype "passive"))
      (node (ref "IC2") (pin "3") (pinfunction "A2_3") (pintype "passive"))
      (node (ref "IC2") (pin "4") (pinfunction "GND_4") (pintype "passive"))
      (node (ref "J7") (pin "3") (pinfunction "3_3") (pintype "passive"))
      (node (ref "J8") (pin "3") (pinfunction "3_3") (pintype "passive"))
      (node (ref "J8") (pin "5") (pinfunction "5_5") (pintype "passive"))
      (node (ref "J8") (pin "9") (pinfunction "9_9") (pintype "passive"))
      (node (ref "R102") (pin "1") (pinfunction "1_1") (pintype "passive"))
      (node (ref "R111") (pin "2") (pinfunction "2_2") (pintype "passive"))
      (node (ref "R112") (pin "1") (pinfunction "1_1") (pintype "passive"))
      (node (ref "R113") (pin "1") (pinfunction "1_1") (pintype "passive"))
      (node (ref "R114") (pin "1") (pinfunction "1_1") (pintype "passive"))
      (node (ref "R115") (pin "1") (pinfunction "1_1") (pintype "passive"))
      (node (ref "R116") (pin "2") (pinfunction "2_2") (pintype "passive"))
      (node (ref "R81") (pin "2") (pinfunction "2_2") (pintype "passive"))
      (node (ref "R86") (pin "2") (pinfunction "2_2") (pintype "passive"))
      (node (ref "U14") (pin "107") (pinfunction "VSS_107") (pintype "power_in"))
      (node (ref "U14") (pin "120") (pinfunction "VSS_120") (pintype "power_in"))
      (node (ref "U14") (pin "130") (pinfunction "VSS_130") (pintype "power_in"))
      (node (ref "U14") (pin "16") (pinfunction "VSS_16") (pintype "bidirectional"))
      (node (ref "U14") (pin "31") (pinfunction "VSSA_31") (pintype "power_in"))
      (node (ref "U14") (pin "38") (pinfunction "VSS_38") (pintype "power_in"))
      (node (ref "U14") (pin "51") (pinfunction "VSS_51") (pintype "power_in"))
      (node (ref "U14") (pin "61") (pinfunction "VSS_61") (pintype "power_in"))
      (node (ref "U14") (pin "83") (pinfunction "VSS_83") (pintype "power_in"))
      (node (ref "U14") (pin "94") (pinfunction "VSS_94") (pintype "power_in"))
    )
    (net (code "94") (name "Net-(D31-K)") (class "Default")
      (node (ref "D31") (pin "2") (pinfunction "K_2") (pintype "passive"))
      (node (ref "R98") (pin "2") (pinfunction "2_2") (pintype "passive"))
    )
    (net (code "95") (name "Net-(D33-Pad2)") (class "Default")
      (node (ref "D33") (pin "2") (pinfunction "2_2") (pintype "passive"))
      (node (ref "R81") (pin "1") (pinfunction "1_1") (pintype "passive"))
    )
    (net (code "96") (name "Net-(D34-Pad2)") (class "Default")
      (node (ref "D34") (pin "2") (pinfunction "2_2") (pintype "passive"))
      (node (ref "R86") (pin "1") (pinfunction "1_1") (pintype "passive"))
    )
    (net (code "97") (name "Net-(D35-Pad2)") (class "Default")
      (node (ref "D35") (pin "2") (pinfunction "2_2") (pintype "passive"))
      (node (ref "R116") (pin "1") (pinfunction "1_1") (pintype "passive"))
    )
    (net (code "98") (name "Net-(IC2-WP)") (class "Default")
      (node (ref "IC2") (pin "7") (pinfunction "WP_7") (pintype "passive"))
      (node (ref "R102") (pin "2") (pinfunction "2_2") (pintype "passive"))
    )
    (net (code "99") (name "Net-(J8-Pad6)") (class "Default")
      (node (ref "J8") (pin "6") (pinfunction "6_6") (pintype "passive"))
      (node (ref "R105") (pin "2") (pinfunction "2_2") (pintype "passive"))
    )
    (net (code "100") (name "Net-(Q8-B)") (class "Default")
      (node (ref "Q8") (pin "1") (pinfunction "B_1") (pintype "passive"))
      (node (ref "R103") (pin "1") (pinfunction "1_1") (pintype "passive"))
      (node (ref "R110") (pin "1") (pinfunction "1_1") (pintype "passive"))
    )
    (net (code "101") (name "Net-(U14A-PC0)") (class "Default")
      (node (ref "C62") (pin "1") (pinfunction "1_1") (pintype "passive"))
      (node (ref "R93") (pin "1") (pinfunction "1_1") (pintype "passive"))
      (node (ref "U14") (pin "26") (pinfunction "PC0_26") (pintype "passive"))
    )
    (net (code "102") (name "Net-(U14A-PC1)") (class "Default")
      (node (ref "C63") (pin "1") (pinfunction "1_1") (pintype "passive"))
      (node (ref "R94") (pin "1") (pinfunction "1_1") (pintype "passive"))
      (node (ref "U14") (pin "27") (pinfunction "PC1_27") (pintype "passive"))
    )
    (net (code "103") (name "Net-(U14A-PC2)") (class "Default")
      (node (ref "C64") (pin "1") (pinfunction "1_1") (pintype "passive"))
      (node (ref "R95") (pin "1") (pinfunction "1_1") (pintype "passive"))
      (node (ref "U14") (pin "28") (pinfunction "PC2_28") (pintype "passive"))
    )
    (net (code "104") (name "Net-(U14B-PF3)") (class "Default")
      (node (ref "R96") (pin "2") (pinfunction "2_2") (pintype "passive"))
      (node (ref "U14") (pin "13") (pinfunction "PF3_13") (pintype "passive"))
    )
    (net (code "105") (name "Net-(U14B-PF4)") (class "Default")
      (node (ref "R97") (pin "2") (pinfunction "2_2") (pintype "passive"))
      (node (ref "U14") (pin "14") (pinfunction "PF4_14") (pintype "passive"))
    )
    (net (code "106") (name "Net-(U14C-VBAT)") (class "Default")
      (node (ref "C66") (pin "2") (pinfunction "2_2") (pintype "passive"))
      (node (ref "C67") (pin "2") (pinfunction "2_2") (pintype "passive"))
      (node (ref "C68") (pin "2") (pinfunction "2_2") (pintype "passive"))
      (node (ref "C69") (pin "2") (pinfunction "2_2") (pintype "passive"))
      (node (ref "C70") (pin "2") (pinfunction "2_2") (pintype "passive"))
      (node (ref "C71") (pin "2") (pinfunction "2_2") (pintype "passive"))
      (node (ref "C72") (pin "2") (pinfunction "2_2") (pintype "passive"))
      (node (ref "C75") (pin "2") (pinfunction "2_2") (pintype "passive"))
      (node (ref "C76") (pin "2") (pinfunction "2_2") (pintype "passive"))
      (node (ref "C77") (pin "2") (pinfunction "2_2") (pintype "passive"))
      (node (ref "C78") (pin "2") (pinfunction "2_2") (pintype "passive"))
      (node (ref "C79") (pin "2") (pinfunction "2_2") (pintype "passive"))
      (node (ref "C80") (pin "2") (pinfunction "2_2") (pintype "passive"))
      (node (ref "C81") (pin "2") (pinfunction "2_2") (pintype "passive"))
      (node (ref "FB6") (pin "1") (pinfunction "1_1") (pintype "passive"))
      (node (ref "FB7") (pin "1") (pinfunction "1_1") (pintype "passive"))
      (node (ref "U14") (pin "108") (pinfunction "VDD_108") (pintype "power_in"))
      (node (ref "U14") (pin "121") (pinfunction "VDD_121") (pintype "power_in"))
      (node (ref "U14") (pin "131") (pinfunction "VDD_131") (pintype "power_in"))
      (node (ref "U14") (pin "144") (pinfunction "VDD_144") (pintype "power_in"))
      (node (ref "U14") (pin "17") (pinfunction "VDD_17") (pintype "bidirectional"))
      (node (ref "U14") (pin "30") (pinfunction "VDD_30") (pintype "power_in"))
      (node (ref "U14") (pin "39") (pinfunction "VDD_39") (pintype "power_in"))
      (node (ref "U14") (pin "52") (pinfunction "VDD_52") (pintype "power_in"))
      (node (ref "U14") (pin "6") (pinfunction "VBAT_6") (pintype "power_in"))
      (node (ref "U14") (pin "62") (pinfunction "VDD_62") (pintype "power_in"))
      (node (ref "U14") (pin "72") (pinfunction "VDD_72") (pintype "power_in"))
      (node (ref "U14") (pin "84") (pinfunction "VDD_84") (pintype "power_in"))
      (node (ref "U14") (pin "95") (pinfunction "VDDUSB_95") (pintype "power_in"))
    )
    (net (code "107") (name "Net-(U14C-VCAP_1)") (class "Default")
      (node (ref "C83") (pin "2") (pinfunction "2_2") (pintype "passive"))
      (node (ref "U14") (pin "71") (pinfunction "VCAP_1_71") (pintype "power_in"))
    )
    (net (code "108") (name "Net-(U14C-VCAP_2)") (class "Default")
      (node (ref "C82") (pin "2") (pinfunction "2_2") (pintype "passive"))
      (node (ref "U14") (pin "106") (pinfunction "VCAP_2_106") (pintype "power_in"))
    )
    (net (code "109") (name "PGND") (class "Default")
      (node (ref "D32") (pin "2") (pinfunction "A_2") (pintype "passive"))
      (node (ref "FB8") (pin "1") (pinfunction "1_1") (pintype "passive"))
      (node (ref "R99") (pin "1") (pinfunction "1_1") (pintype "passive"))
    )
    (net (code "110") (name "unconnected-(J6-Pad1)") (class "Default")
      (node (ref "J6") (pin "1") (pinfunction "1_1") (pintype "passive"))
    )
    (net (code "111") (name "unconnected-(J6-Pad2)") (class "Default")
      (node (ref "J6") (pin "2") (pinfunction "2_2") (pintype "passive"))
    )
    (net (code "112") (name "unconnected-(J6-Pad3)") (class "Default")
      (node (ref "J6") (pin "3") (pinfunction "3_3") (pintype "passive"))
    )
    (net (code "113") (name "unconnected-(J6-Pad4)") (class "Default")
      (node (ref "J6") (pin "4") (pinfunction "4_4") (pintype "passive"))
    )
    (net (code "114") (name "unconnected-(J6-Pad5)") (class "Default")
      (node (ref "J6") (pin "5") (pinfunction "5_5") (pintype "passive"))
    )
    (net (code "115") (name "unconnected-(J6-Pad6)") (class "Default")
      (node (ref "J6") (pin "6") (pinfunction "6_6") (pintype "passive"))
    )
    (net (code "116") (name "unconnected-(J6-Pad7)") (class "Default")
      (node (ref "J6") (pin "7") (pinfunction "7_7") (pintype "passive"))
    )
    (net (code "117") (name "unconnected-(J6-Pad8)") (class "Default")
      (node (ref "J6") (pin "8") (pinfunction "8_8") (pintype "passive"))
    )
    (net (code "118") (name "unconnected-(J6-Pad9)") (class "Default")
      (node (ref "J6") (pin "9") (pinfunction "9_9") (pintype "passive"))
    )
    (net (code "119") (name "unconnected-(J6-Pad10)") (class "Default")
      (node (ref "J6") (pin "10") (pinfunction "10_10") (pintype "passive"))
    )
    (net (code "120") (name "unconnected-(U14A-PA8-Pad100)") (class "Default")
      (node (ref "U14") (pin "100") (pinfunction "PA8_100") (pintype "passive"))
    )
    (net (code "121") (name "unconnected-(U14A-PA15-Pad110)") (class "Default")
      (node (ref "U14") (pin "110") (pinfunction "PA15_110") (pintype "passive"))
    )
    (net (code "122") (name "unconnected-(U14A-PB1-Pad47)") (class "Default")
      (node (ref "U14") (pin "47") (pinfunction "PB1_47") (pintype "passive"))
    )
    (net (code "123") (name "unconnected-(U14A-PB3-Pad133)") (class "Default")
      (node (ref "U14") (pin "133") (pinfunction "PB3_133") (pintype "passive"))
    )
    (net (code "124") (name "unconnected-(U14A-PB4-Pad134)") (class "Default")
      (node (ref "U14") (pin "134") (pinfunction "PB4_134") (pintype "passive"))
    )
    (net (code "125") (name "unconnected-(U14A-PB9-Pad140)") (class "Default")
      (node (ref "U14") (pin "140") (pinfunction "PB9_140") (pintype "passive"))
    )
    (net (code "126") (name "unconnected-(U14A-PB10-Pad69)") (class "Default")
      (node (ref "U14") (pin "69") (pinfunction "PB10_69") (pintype "passive"))
    )
    (net (code "127") (name "unconnected-(U14A-PB11-Pad70)") (class "Default")
      (node (ref "U14") (pin "70") (pinfunction "PB11_70") (pintype "passive"))
    )
    (net (code "128") (name "unconnected-(U14A-PB12-Pad73)") (class "Default")
      (node (ref "U14") (pin "73") (pinfunction "PB12_73") (pintype "passive"))
    )
    (net (code "129") (name "unconnected-(U14A-PB13-Pad74)") (class "Default")
      (node (ref "U14") (pin "74") (pinfunction "PB13_74") (pintype "passive"))
    )
    (net (code "130") (name "unconnected-(U14A-PB14-Pad75)") (class "Default")
      (node (ref "U14") (pin "75") (pinfunction "PB14_75") (pintype "passive"))
    )
    (net (code "131") (name "unconnected-(U14A-PB15-Pad76)") (class "Default")
      (node (ref "U14") (pin "76") (pinfunction "PB15_76") (pintype "passive"))
    )
    (net (code "132") (name "unconnected-(U14A-PC6-Pad96)") (class "Default")
      (node (ref "U14") (pin "96") (pinfunction "PC6_96") (pintype "passive"))
    )
    (net (code "133") (name "unconnected-(U14A-PC7-Pad97)") (class "Default")
      (node (ref "U14") (pin "97") (pinfunction "PC7_97") (pintype "passive"))
    )
    (net (code "134") (name "unconnected-(U14A-PC8-Pad98)") (class "Default")
      (node (ref "U14") (pin "98") (pinfunction "PC8_98") (pintype "passive"))
    )
    (net (code "135") (name "unconnected-(U14A-PC9-Pad99)") (class "Default")
      (node (ref "U14") (pin "99") (pinfunction "PC9_99") (pintype "passive"))
    )
    (net (code "136") (name "unconnected-(U14A-PC10-Pad111)") (class "Default")
      (node (ref "U14") (pin "111") (pinfunction "PC10_111") (pintype "passive"))
    )
    (net (code "137") (name "unconnected-(U14A-PC11-Pad112)") (class "Default")
      (node (ref "U14") (pin "112") (pinfunction "PC11_112") (pintype "passive"))
    )
    (net (code "138") (name "unconnected-(U14A-PC12-Pad113)") (class "Default")
      (node (ref "U14") (pin "113") (pinfunction "PC12_113") (pintype "passive"))
    )
    (net (code "139") (name "unconnected-(U14A-PC15-OSC32_OUT-Pad9)") (class "Default")
      (node (ref "U14") (pin "9") (pinfunction "PC15-OSC32_OUT_9") (pintype "passive"))
    )
    (net (code "140") (name "unconnected-(U14A-PD2-Pad116)") (class "Default")
      (node (ref "U14") (pin "116") (pinfunction "PD2_116") (pintype "passive"))
    )
    (net (code "141") (name "unconnected-(U14A-PD3-Pad117)") (class "Default")
      (node (ref "U14") (pin "117") (pinfunction "PD3_117") (pintype "passive"))
    )
    (net (code "142") (name "unconnected-(U14A-PD4-Pad118)") (class "Default")
      (node (ref "U14") (pin "118") (pinfunction "PD4_118") (pintype "passive"))
    )
    (net (code "143") (name "unconnected-(U14A-PD5-Pad119)") (class "Default")
      (node (ref "U14") (pin "119") (pinfunction "PD5_119") (pintype "passive"))
    )
    (net (code "144") (name "unconnected-(U14A-PD6-Pad122)") (class "Default")
      (node (ref "U14") (pin "122") (pinfunction "PD6_122") (pintype "passive"))
    )
    (net (code "145") (name "unconnected-(U14A-PD8-Pad77)") (class "Default")
      (node (ref "U14") (pin "77") (pinfunction "PD8_77") (pintype "passive"))
    )
    (net (code "146") (name "unconnected-(U14A-PD9-Pad78)") (class "Default")
      (node (ref "U14") (pin "78") (pinfunction "PD9_78") (pintype "passive"))
    )
    (net (code "147") (name "unconnected-(U14A-PD13-Pad82)") (class "Default")
      (node (ref "U14") (pin "82") (pinfunction "PD13_82") (pintype "passive"))
    )
    (net (code "148") (name "unconnected-(U14A-PD14-Pad85)") (class "Default")
      (node (ref "U14") (pin "85") (pinfunction "PD14_85") (pintype "passive"))
    )
    (net (code "149") (name "unconnected-(U14A-PD15-Pad86)") (class "Default")
      (node (ref "U14") (pin "86") (pinfunction "PD15_86") (pintype "passive"))
    )
    (net (code "150") (name "unconnected-(U14B-PE0-Pad141)") (class "Default")
      (node (ref "U14") (pin "141") (pinfunction "PE0_141") (pintype "passive"))
    )
    (net (code "151") (name "unconnected-(U14B-PE15-Pad68)") (class "Default")
      (node (ref "U14") (pin "68") (pinfunction "PE15_68") (pintype "passive"))
    )
    (net (code "152") (name "unconnected-(U14B-PF0-Pad10)") (class "Default")
      (node (ref "U14") (pin "10") (pinfunction "PF0_10") (pintype "passive"))
    )
    (net (code "153") (name "unconnected-(U14B-PF1-Pad11)") (class "Default")
      (node (ref "U14") (pin "11") (pinfunction "PF1_11") (pintype "passive"))
    )
    (net (code "154") (name "unconnected-(U14B-PF2-Pad12)") (class "Default")
      (node (ref "U14") (pin "12") (pinfunction "PF2_12") (pintype "passive"))
    )
    (net (code "155") (name "unconnected-(U14B-PF5-Pad15)") (class "Default")
      (node (ref "U14") (pin "15") (pinfunction "PF5_15") (pintype "passive"))
    )
    (net (code "156") (name "unconnected-(U14B-PF6-Pad18)") (class "Default")
      (node (ref "U14") (pin "18") (pinfunction "PF6_18") (pintype "passive"))
    )
    (net (code "157") (name "unconnected-(U14B-PF7-Pad19)") (class "Default")
      (node (ref "U14") (pin "19") (pinfunction "PF7_19") (pintype "passive"))
    )
    (net (code "158") (name "unconnected-(U14B-PF8-Pad20)") (class "Default")
      (node (ref "U14") (pin "20") (pinfunction "PF8_20") (pintype "passive"))
    )
    (net (code "159") (name "unconnected-(U14B-PF9-Pad21)") (class "Default")
      (node (ref "U14") (pin "21") (pinfunction "PF9_21") (pintype "passive"))
    )
    (net (code "160") (name "unconnected-(U14B-PF10-Pad22)") (class "Default")
      (node (ref "U14") (pin "22") (pinfunction "PF10_22") (pintype "passive"))
    )
    (net (code "161") (name "unconnected-(U14B-PF11-Pad49)") (class "Default")
      (node (ref "U14") (pin "49") (pinfunction "PF11_49") (pintype "passive"))
    )
    (net (code "162") (name "unconnected-(U14B-PF12-Pad50)") (class "Default")
      (node (ref "U14") (pin "50") (pinfunction "PF12_50") (pintype "passive"))
    )
    (net (code "163") (name "unconnected-(U14B-PG2-Pad87)") (class "Default")
      (node (ref "U14") (pin "87") (pinfunction "PG2_87") (pintype "passive"))
    )
    (net (code "164") (name "unconnected-(U14B-PG11-Pad126)") (class "Default")
      (node (ref "U14") (pin "126") (pinfunction "PG11_126") (pintype "passive"))
    )
    (net (code "165") (name "unconnected-(U14B-PG12-Pad127)") (class "Default")
      (node (ref "U14") (pin "127") (pinfunction "PG12_127") (pintype "passive"))
    )
    (net (code "166") (name "unconnected-(U14B-PG13-Pad128)") (class "Default")
      (node (ref "U14") (pin "128") (pinfunction "PG13_128") (pintype "passive"))
    )
  )
)
